# MCU.net
KiCad netlist of a schematic drawn in Altium Designer
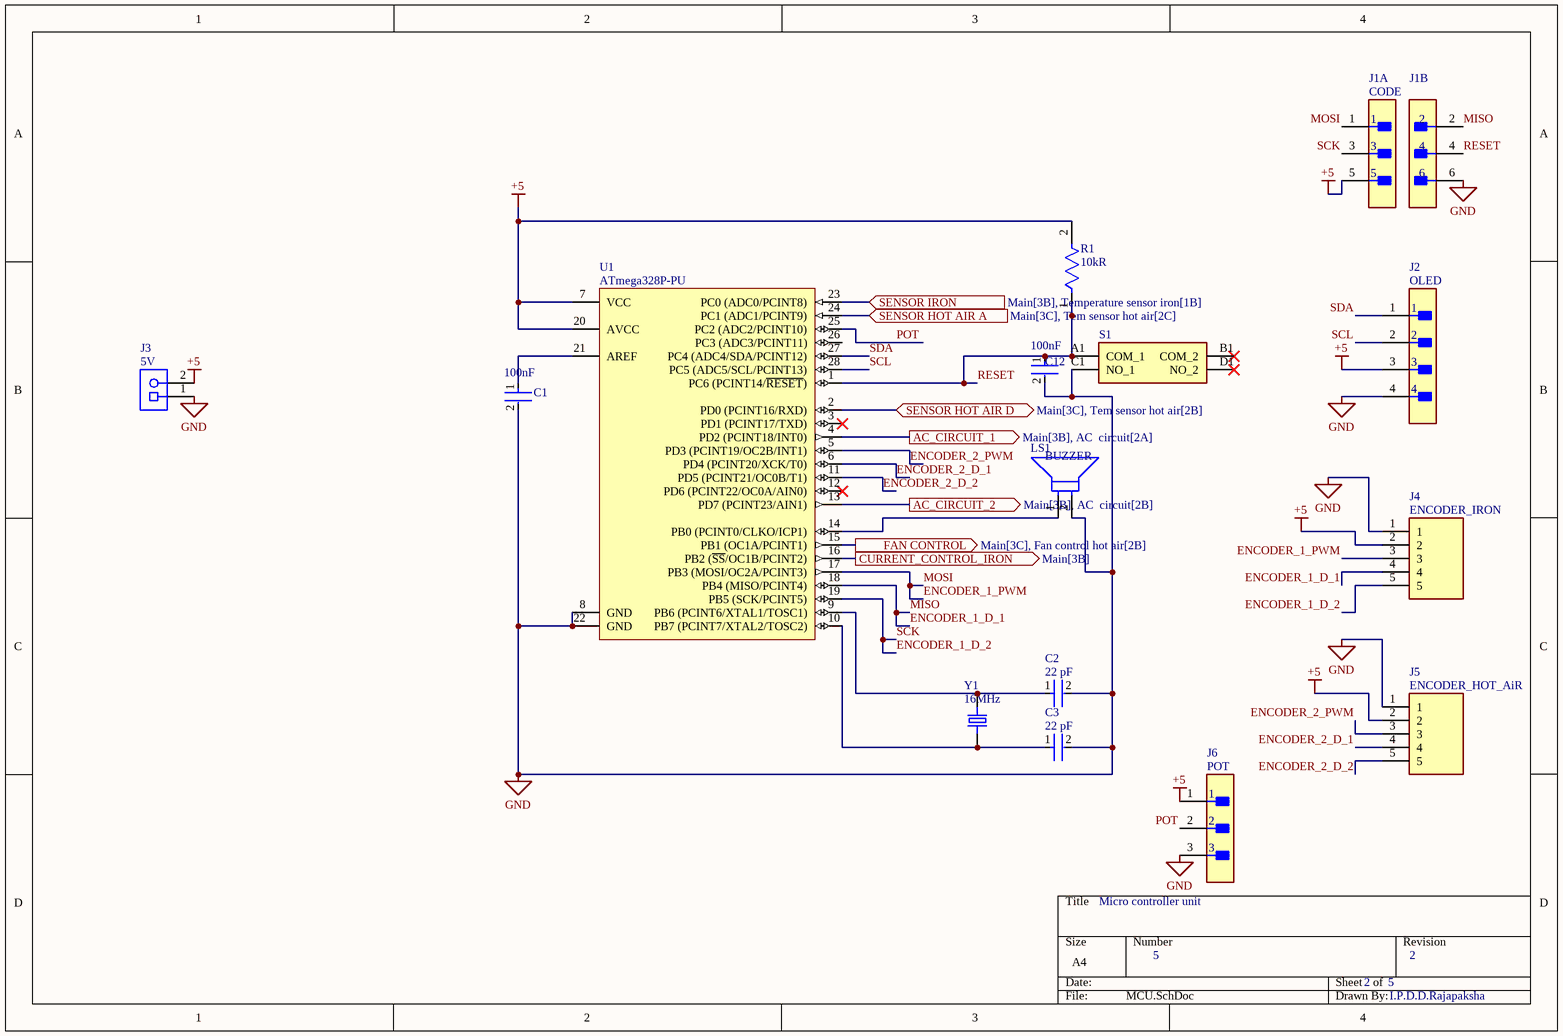
[diagram p0: MCU.SchDoc]

(export (version "E")
  (design (tool "Eeschema 10.0.6"))
  (components
    (comp (ref "C1")
      (value "0805YC104M4T2A")
      (footprint "FP-0805-L_2_01_0_2-W_1_25-IPC_A")
      (description "Automotive Ceramic Capacitor, 0805, 100nF, 20%, X7R, 0.15, 16V")
      (fields (field (name "CAPACITANCE") "100nF") (field (name "TOLERANCE") "20%"))
      (libsource (lib "Altium Content Vault") (part "02cd4be3c70576c341d710602a673aa"))
    )
    (comp (ref "C2")
      (value "C0805C220J5GACTU")
      (footprint "FP-C0805C-DN-MFG")
      (description "Capacitor; Ceramic; Cap; 22.0pF; Tol 5%; SMT; Vol-Rtg 50V; C0G; Tape and Reel")
      (fields
        (field (name "CAPACITANCE") "22 pF")
        (field (name "OCTOPART") "https://octopart.com/c0805c220j5gactu-kemet-145470")
        (field (name "MANUFACTURER") "KEMET")
      )
      (libsource (lib "Altium Content Vault") (part "b4654b650e69147ec39a6b967a45e02"))
    )
    (comp (ref "C3")
      (value "C0805C220J5GACTU")
      (footprint "FP-C0805C-DN-MFG")
      (description "Capacitor; Ceramic; Cap; 22.0pF; Tol 5%; SMT; Vol-Rtg 50V; C0G; Tape and Reel")
      (fields
        (field (name "CAPACITANCE") "22 pF")
        (field (name "OCTOPART") "https://octopart.com/c0805c220j5gactu-kemet-145470")
        (field (name "MANUFACTURER") "KEMET")
      )
      (libsource (lib "Altium Content Vault") (part "b4654b650e69147ec39a6b967a45e02"))
    )
    (comp (ref "C12")
      (value "0805YC104M4T2A")
      (footprint "FP-0805-L_2_01_0_2-W_1_25-IPC_A")
      (description "Automotive Ceramic Capacitor, 0805, 100nF, 20%, X7R, 0.15, 16V")
      (fields (field (name "CAPACITANCE") "100nF") (field (name "TOLERANCE") "20%"))
      (libsource (lib "Altium Content Vault") (part "02cd4be3c70576c341d710602a673aa"))
    )
    (comp (ref "J1")
      (value "90131-0763")
      (footprint "FP-90131-0763-MFG")
      (description "90131-0763 Conn Unshrouded Header HDR 6 POS 2.54mm Solder ST Top Entry Thru-Hole C-Grid III™ Tray")
      (fields (field (name "PARAMETER 1") "CODE"))
      (libsource (lib "") (part "2654a11fb13586ecb194516b1c997bc_1"))
    )
    (comp (ref "J2")
      (value "OLED")
      (footprint "FP-B4B-XH-A_LF_SN-MFG")
      (description "CONN HEADER VERT 4POS 2.5MM")
      (fields (field (name "Comment") "B4B-XH-A(LF)(SN)"))
      (libsource (lib "Altium Content Vault") (part "299a8cea1bdcbc3624fe62c390fa72c"))
    )
    (comp (ref "J3")
      (value "1729128")
      (footprint "PHOE-1729128-2_V")
      (description "PCB Terminal Block, 13.5 A, 400 V, 2-Pin THD, RoHS, Bulk")
      (fields (field (name "MANUFACTURER") "Phoenix Contact") (field (name "PARAMETER 1") "5V"))
      (libsource (lib "Altium Content Vault") (part "CN-2P-F-R2"))
    )
    (comp (ref "J4")
      (value "B5B-XH-AM__LF__SN_")
      (footprint "SamacSys:B5BXHAMLFSN")
      (description "Connector")
      (fields
        (field (name "MANUFACTURER_PART_NUMBER") "B5B-XH-AM (LF)(SN)")
        (field (name "PARAMETER 1") "ENCODER_IRON")
      )
      (libsource (lib "*") (part "B5B-XH-AM__LF__SN_"))
    )
    (comp (ref "J5")
      (value "B5B-XH-AM__LF__SN_")
      (footprint "SamacSys:B5BXHAMLFSN")
      (description "Connector")
      (fields
        (field (name "MANUFACTURER_PART_NUMBER") "B5B-XH-AM (LF)(SN)")
        (field (name "PARAMETER 1") "ENCODER_HOT_AiR")
      )
      (libsource (lib "*") (part "B5B-XH-AM__LF__SN_"))
    )
    (comp (ref "J6")
      (value "B3B-XH-A(LF)(SN)")
      (footprint "FP-B3B-XH-A_LF_SN-MFG")
      (description "CONN HEADER VERT 3POS 2.5MM")
      (fields (field (name "PARAMETER 1") "POT"))
      (libsource (lib "Altium Content Vault") (part "0d3f023dd272f625e17a2be33dea85f"))
    )
    (comp (ref "LS1")
      (value "AI-1223-TWT-5V-R")
      (footprint "FP-AI-1223-TWT-5V-R-MFG")
      (description "AUDIO MAGNETIC INDICATOR 3-7V TH")
      (fields (field (name "PARAMETER 1") "BUZZER"))
      (libsource (lib "Altium Content Vault") (part "1973c4b650225fd2ddacaff6b763965"))
    )
    (comp (ref "R1")
      (value "CRCW120610K0FKEA")
      (footprint "FP-CRCW1206-e3-IPC_C")
      (description "RES Thick Film, 10kΩ, 1%, 0.25W, 100ppm/°C, 1206")
      (fields (field (name "TOLERANCE") "1%") (field (name "RESISTANCE") "10kR"))
      (libsource (lib "Altium Content Vault") (part "1029c3af85768c4190bb7ad29bc67b5"))
    )
    (comp (ref "S1")
      (value "TS-1187A-B-A-B")
      (footprint "SamacSys:TS1187ABAB")
      (description "Switch")
      (libsource (lib "*") (part "TS-1187A-B-A-B"))
    )
    (comp (ref "U1")
      (value "ATmega328P-PU")
      (footprint "28P3")
      (libsource (lib "Altium Content Vault") (part "MC-8B-ATM48-IL28"))
    )
    (comp (ref "Y1")
      (value "16MHz")
      (footprint "XTAL_ECS-160-20-4X")
      (description "16MHz Â±30ppm Crystal Series 40 Ohms HC-49/US")
      (fields (field (name "MF") "ECS Inc.") (field (name "MP") "ECS-160-S-4"))
      (libsource (lib "ECS-160-S-4") (part "ECS-160-S-4"))
    )
  )
  (nets
    (net (code "1") (name "+5") (class "Default")
      (node (ref "J1") (pin "5") (pinfunction "5_5") (pintype "passive"))
      (node (ref "J2") (pin "3") (pinfunction "3_3") (pintype "passive"))
      (node (ref "J3") (pin "2") (pinfunction "2_2") (pintype "passive"))
      (node (ref "J4") (pin "2") (pinfunction "2_2") (pintype "passive"))
      (node (ref "J5") (pin "2") (pinfunction "2_2") (pintype "passive"))
      (node (ref "J6") (pin "1") (pinfunction "1_1") (pintype "passive"))
      (node (ref "R1") (pin "2") (pinfunction "2_2") (pintype "passive"))
      (node (ref "U1") (pin "20") (pinfunction "AVCC_20") (pintype "power_in"))
      (node (ref "U1") (pin "7") (pinfunction "VCC_7") (pintype "power_in"))
    )
    (net (code "2") (name "/AC_CIRCUIT_1") (class "Default")
      (node (ref "U1") (pin "4") (pinfunction "PD2_(PCINT18/INT0)_4") (pintype "output"))
    )
    (net (code "3") (name "/AC_CIRCUIT_2") (class "Default")
      (node (ref "U1") (pin "13") (pinfunction "PD7_(PCINT23/AIN1)_13") (pintype "output"))
    )
    (net (code "4") (name "/CURRENT_CONTROL_IRON") (class "Default")
      (node (ref "U1") (pin "16") (pinfunction "PB2_(~{SS}/OC1B/PCINT2)_16") (pintype "output"))
    )
    (net (code "5") (name "/ENCODER_1_D_1") (class "Default")
      (node (ref "J1") (pin "2") (pinfunction "2_2") (pintype "passive"))
      (node (ref "J4") (pin "4") (pinfunction "4_4") (pintype "passive"))
      (node (ref "U1") (pin "18") (pinfunction "PB4_(MISO/PCINT4)_18") (pintype "bidirectional"))
    )
    (net (code "6") (name "/ENCODER_1_D_2") (class "Default")
      (node (ref "J1") (pin "3") (pinfunction "3_3") (pintype "passive"))
      (node (ref "J4") (pin "5") (pinfunction "5_5") (pintype "passive"))
      (node (ref "U1") (pin "19") (pinfunction "PB5_(SCK/PCINT5)_19") (pintype "bidirectional"))
    )
    (net (code "7") (name "/ENCODER_1_PWM") (class "Default")
      (node (ref "J1") (pin "1") (pinfunction "1_1") (pintype "passive"))
      (node (ref "J4") (pin "3") (pinfunction "3_3") (pintype "passive"))
      (node (ref "U1") (pin "17") (pinfunction "PB3_(MOSI/OC2A/PCINT3)_17") (pintype "output"))
    )
    (net (code "8") (name "/ENCODER_2_D_1") (class "Default")
      (node (ref "J5") (pin "4") (pinfunction "4_4") (pintype "passive"))
      (node (ref "U1") (pin "6") (pinfunction "PD4_(PCINT20/XCK/T0)_6") (pintype "bidirectional"))
    )
    (net (code "9") (name "/ENCODER_2_D_2") (class "Default")
      (node (ref "J5") (pin "5") (pinfunction "5_5") (pintype "passive"))
      (node (ref "U1") (pin "11") (pinfunction "PD5_(PCINT21/OC0B/T1)_11") (pintype "bidirectional"))
    )
    (net (code "10") (name "/ENCODER_2_PWM") (class "Default")
      (node (ref "J5") (pin "3") (pinfunction "3_3") (pintype "passive"))
      (node (ref "U1") (pin "5") (pinfunction "PD3_(PCINT19/OC2B/INT1)_5") (pintype "bidirectional"))
    )
    (net (code "11") (name "/FAN CONTROL") (class "Default")
      (node (ref "U1") (pin "15") (pinfunction "PB1_(OC1A/PCINT1)_15") (pintype "output"))
    )
    (net (code "12") (name "/POT") (class "Default")
      (node (ref "J6") (pin "2") (pinfunction "2_2") (pintype "passive"))
      (node (ref "U1") (pin "25") (pinfunction "PC2_(ADC2/PCINT10)_25") (pintype "bidirectional"))
    )
    (net (code "13") (name "/RESET") (class "Default")
      (node (ref "C12") (pin "1") (pinfunction "1_1") (pintype "passive"))
      (node (ref "J1") (pin "4") (pinfunction "4_4") (pintype "passive"))
      (node (ref "R1") (pin "1") (pinfunction "1_1") (pintype "passive"))
      (node (ref "S1") (pin "A1") (pinfunction "COM_1_A1") (pintype "passive"))
      (node (ref "U1") (pin "1") (pinfunction "PC6_(PCINT14/~{RESET})_1") (pintype "bidirectional"))
    )
    (net (code "14") (name "/SCL") (class "Default")
      (node (ref "J2") (pin "2") (pinfunction "2_2") (pintype "passive"))
      (node (ref "U1") (pin "28") (pinfunction "PC5_(ADC5/SCL/PCINT13)_28") (pintype "bidirectional"))
    )
    (net (code "15") (name "/SDA") (class "Default")
      (node (ref "J2") (pin "1") (pinfunction "1_1") (pintype "passive"))
      (node (ref "U1") (pin "27") (pinfunction "PC4_(ADC4/SDA/PCINT12)_27") (pintype "bidirectional"))
    )
    (net (code "16") (name "/SENSOR HOT AIR A") (class "Default")
      (node (ref "U1") (pin "24") (pinfunction "PC1_(ADC1/PCINT9)_24") (pintype "input"))
    )
    (net (code "17") (name "/SENSOR HOT AIR D") (class "Default")
      (node (ref "U1") (pin "2") (pinfunction "PD0_(PCINT16/RXD)_2") (pintype "bidirectional"))
    )
    (net (code "18") (name "/SENSOR IRON") (class "Default")
      (node (ref "U1") (pin "23") (pinfunction "PC0_(ADC0/PCINT8)_23") (pintype "input"))
    )
    (net (code "19") (name "GND") (class "Default")
      (node (ref "C1") (pin "2") (pinfunction "2_2") (pintype "passive"))
      (node (ref "C12") (pin "2") (pinfunction "2_2") (pintype "passive"))
      (node (ref "C2") (pin "2") (pinfunction "2_2") (pintype "passive"))
      (node (ref "C3") (pin "2") (pinfunction "2_2") (pintype "passive"))
      (node (ref "J1") (pin "6") (pinfunction "6_6") (pintype "passive"))
      (node (ref "J2") (pin "4") (pinfunction "4_4") (pintype "passive"))
      (node (ref "J3") (pin "1") (pinfunction "1_1") (pintype "passive"))
      (node (ref "J4") (pin "1") (pinfunction "1_1") (pintype "passive"))
      (node (ref "J5") (pin "1") (pinfunction "1_1") (pintype "passive"))
      (node (ref "J6") (pin "3") (pinfunction "3_3") (pintype "passive"))
      (node (ref "LS1") (pin "2") (pinfunction "A_2") (pintype "passive"))
      (node (ref "S1") (pin "C1") (pinfunction "NO_1_C1") (pintype "passive"))
      (node (ref "U1") (pin "22") (pinfunction "GND_22") (pintype "power_in"))
      (node (ref "U1") (pin "8") (pinfunction "GND_8") (pintype "power_in"))
    )
    (net (code "20") (name "Net-(LS1-C)") (class "Default")
      (node (ref "LS1") (pin "1") (pinfunction "C_1") (pintype "passive"))
      (node (ref "U1") (pin "14") (pinfunction "PB0_(PCINT0/CLKO/ICP1)_14") (pintype "bidirectional"))
    )
    (net (code "21") (name "Net-(U1-AREF)") (class "Default")
      (node (ref "C1") (pin "1") (pinfunction "1_1") (pintype "passive"))
      (node (ref "U1") (pin "21") (pinfunction "AREF_21") (pintype "power_in"))
    )
    (net (code "22") (name "Net-(U1-PB6_(PCINT6{slash}XTAL1{slash}TOSC1))") (class "Default")
      (node (ref "C2") (pin "1") (pinfunction "1_1") (pintype "passive"))
      (node (ref "U1") (pin "9") (pinfunction "PB6_(PCINT6/XTAL1/TOSC1)_9") (pintype "bidirectional"))
      (node (ref "Y1") (pin "2") (pinfunction "2_2") (pintype "passive"))
    )
    (net (code "23") (name "Net-(U1-PB7_(PCINT7{slash}XTAL2{slash}TOSC2))") (class "Default")
      (node (ref "C3") (pin "1") (pinfunction "1_1") (pintype "passive"))
      (node (ref "U1") (pin "10") (pinfunction "PB7_(PCINT7/XTAL2/TOSC2)_10") (pintype "bidirectional"))
      (node (ref "Y1") (pin "1") (pinfunction "1_1") (pintype "passive"))
    )
    (net (code "24") (name "unconnected-(S1-COM_2-PadB1)") (class "Default")
      (node (ref "S1") (pin "B1") (pinfunction "COM_2_B1") (pintype "passive+no_connect"))
    )
    (net (code "25") (name "unconnected-(S1-NO_2-PadD1)") (class "Default")
      (node (ref "S1") (pin "D1") (pinfunction "NO_2_D1") (pintype "passive+no_connect"))
    )
    (net (code "26") (name "unconnected-(U1-PC3_(ADC3{slash}PCINT11)-Pad26)") (class "Default")
      (node (ref "U1") (pin "26") (pinfunction "PC3_(ADC3/PCINT11)_26") (pintype "bidirectional"))
    )
    (net (code "27") (name "unconnected-(U1-PD1_(PCINT17{slash}TXD)-Pad3)") (class "Default")
      (node (ref "U1") (pin "3") (pinfunction "PD1_(PCINT17/TXD)_3") (pintype "bidirectional+no_connect"))
    )
    (net (code "28") (name "unconnected-(U1-PD6_(PCINT22{slash}OC0A{slash}AIN0)-Pad12)") (class "Default")
      (node (ref "U1") (pin "12") (pinfunction "PD6_(PCINT22/OC0A/AIN0)_12") (pintype "bidirectional+no_connect"))
    )
  )
)
